# Battery_Detector_v1_0.net
KiCad netlist of a schematic drawn in EAGLE
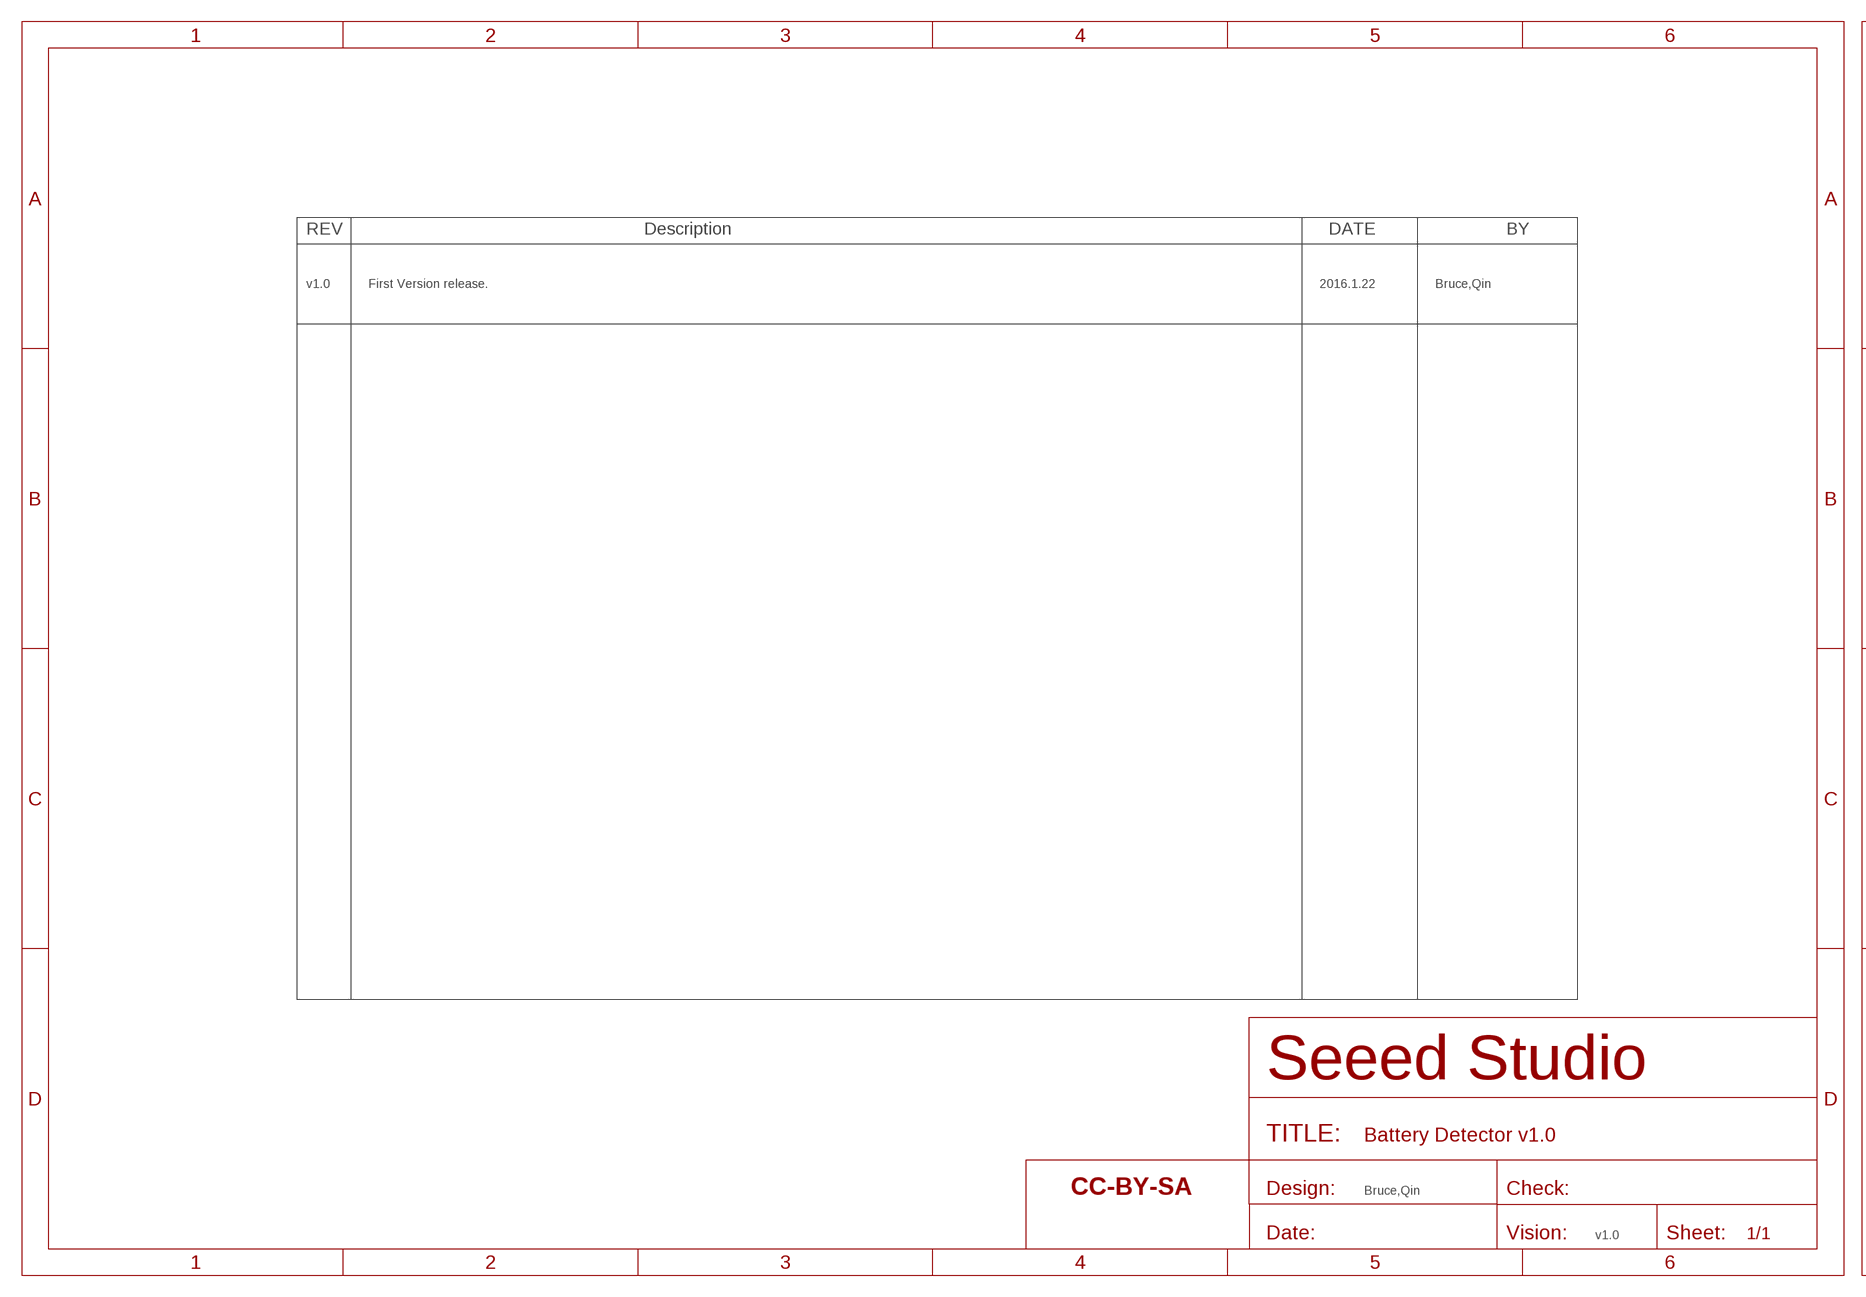
[diagram p0: schematic, sheet 1, part 1 of 2]
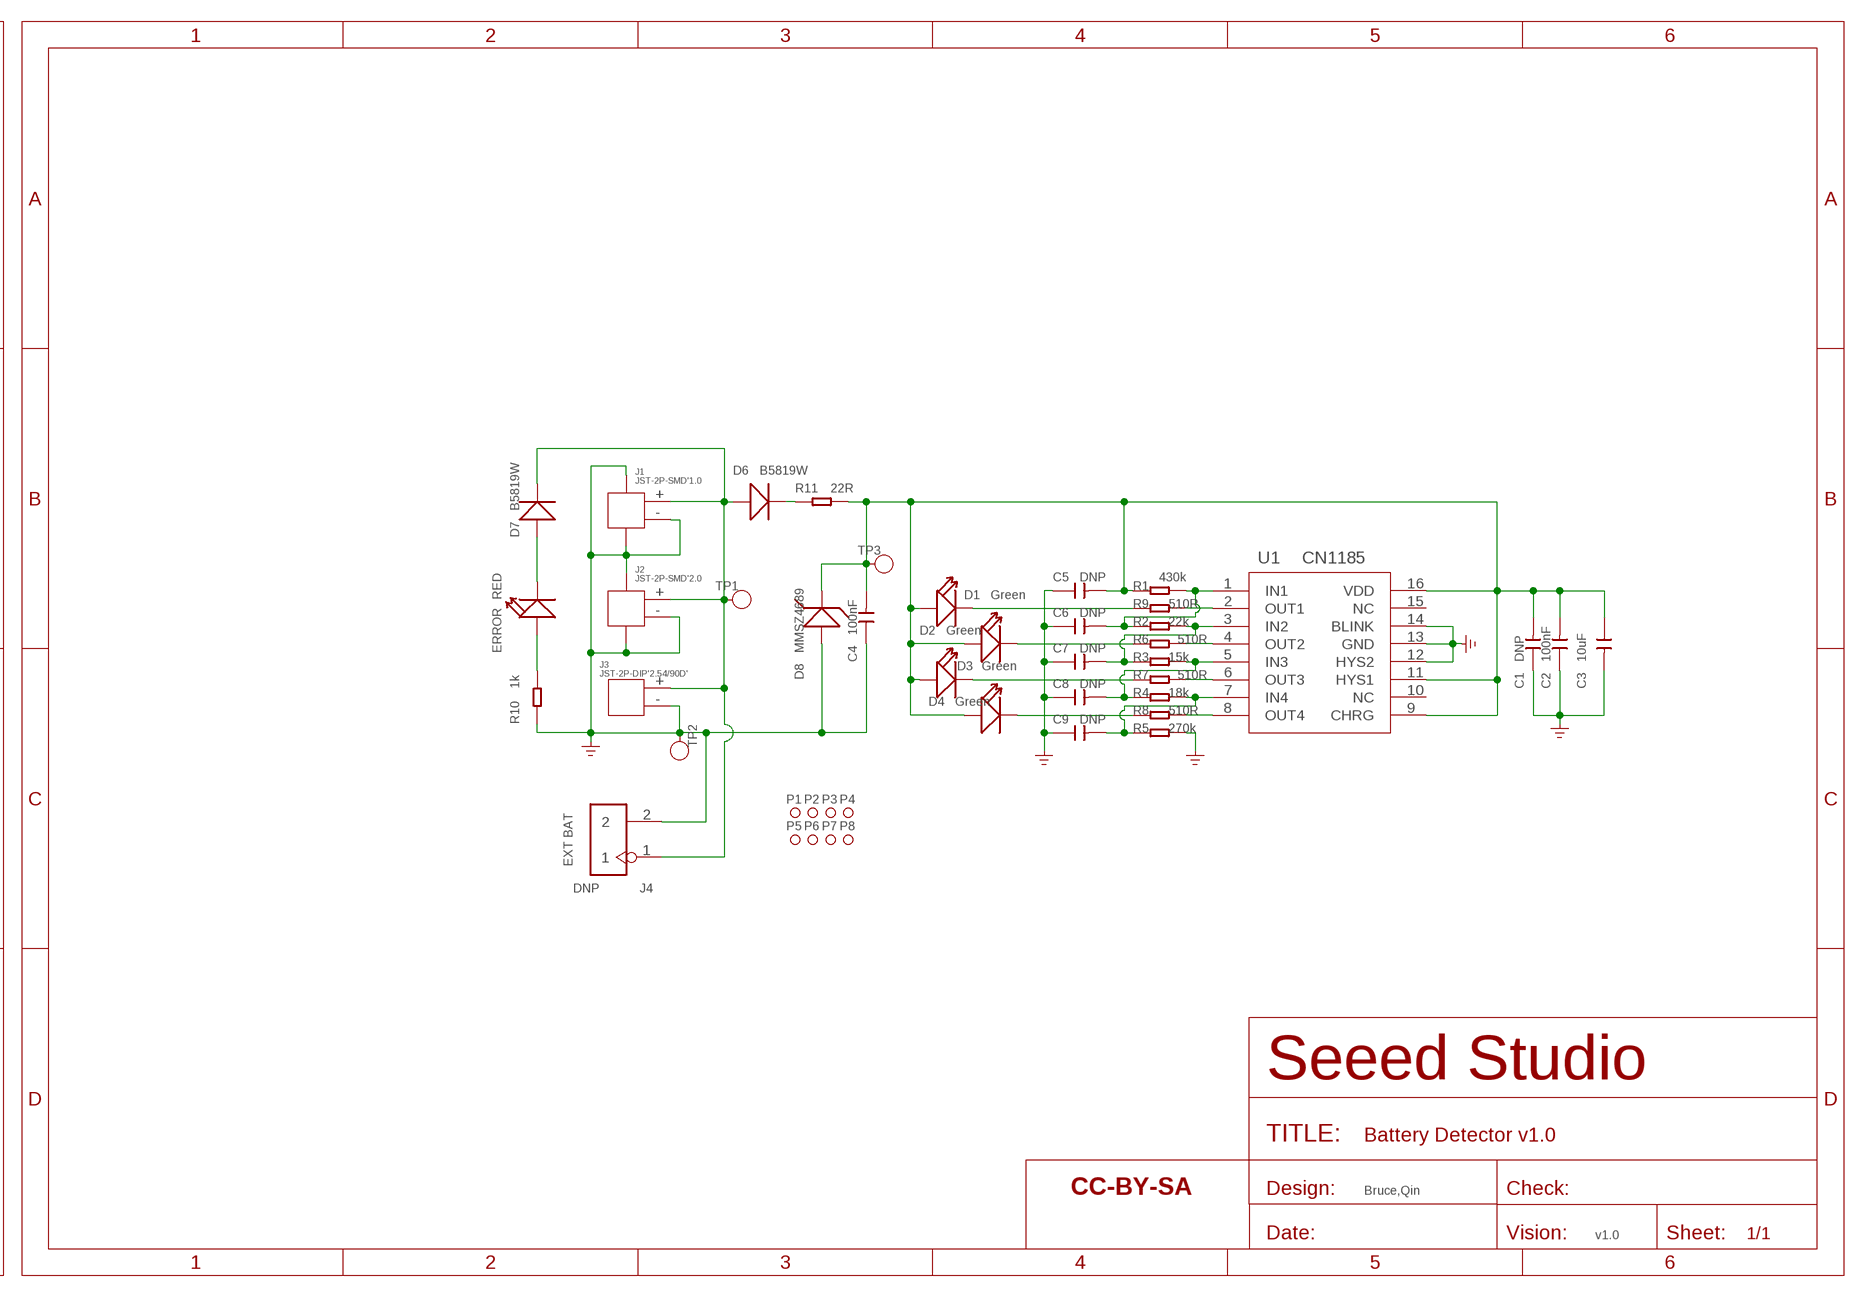
[diagram p1: schematic, sheet 1, part 2 of 2]

(export (version "E")
  (design (tool "Eeschema 10.0.6"))
  (components
    (comp (ref "C1")
      (value "DNP")
      (footprint "eagle-import:C0603")
      (libsource (lib "eagle-import") (part "CAP-0603"))
    )
    (comp (ref "C2")
      (value "100nF")
      (footprint "eagle-import:C0603")
      (libsource (lib "eagle-import") (part "CAP-0603"))
    )
    (comp (ref "C3")
      (value "10uF")
      (footprint "eagle-import:C0805")
      (libsource (lib "eagle-import") (part "CAP-0805"))
    )
    (comp (ref "C4")
      (value "100nF")
      (footprint "eagle-import:C0603")
      (libsource (lib "eagle-import") (part "CAP-0603"))
    )
    (comp (ref "C5")
      (value "DNP")
      (footprint "eagle-import:C0603")
      (libsource (lib "eagle-import") (part "CAP-0603"))
    )
    (comp (ref "C6")
      (value "DNP")
      (footprint "eagle-import:C0603")
      (libsource (lib "eagle-import") (part "CAP-0603"))
    )
    (comp (ref "C7")
      (value "DNP")
      (footprint "eagle-import:C0603")
      (libsource (lib "eagle-import") (part "CAP-0603"))
    )
    (comp (ref "C8")
      (value "DNP")
      (footprint "eagle-import:C0603")
      (libsource (lib "eagle-import") (part "CAP-0603"))
    )
    (comp (ref "C9")
      (value "DNP")
      (footprint "eagle-import:C0603")
      (libsource (lib "eagle-import") (part "CAP-0603"))
    )
    (comp (ref "D1")
      (value "Green")
      (footprint "eagle-import:LED-0603")
      (libsource (lib "eagle-import") (part "LED'0603'"))
    )
    (comp (ref "D2")
      (value "Green")
      (footprint "eagle-import:LED-0603")
      (libsource (lib "eagle-import") (part "LED'0603'"))
    )
    (comp (ref "D3")
      (value "Green")
      (footprint "eagle-import:LED-0603")
      (libsource (lib "eagle-import") (part "LED'0603'"))
    )
    (comp (ref "D4")
      (value "Green")
      (footprint "eagle-import:LED-0603")
      (libsource (lib "eagle-import") (part "LED'0603'"))
    )
    (comp (ref "D6")
      (value "B5819W")
      (footprint "eagle-import:SOD-123")
      (libsource (lib "eagle-import") (part "DIODE'1206'"))
    )
    (comp (ref "D7")
      (value "B5819W")
      (footprint "eagle-import:SOD-123")
      (libsource (lib "eagle-import") (part "DIODE'1206'"))
    )
    (comp (ref "D8")
      (value "MMSZ4689")
      (footprint "eagle-import:SOD-123")
      (libsource (lib "eagle-import") (part "D-ZENER-2P'MMSZ4689-V'"))
    )
    (comp (ref "ERROR")
      (value "RED")
      (footprint "eagle-import:LED-0603")
      (libsource (lib "eagle-import") (part "LED'0603'"))
    )
    (comp (ref "FR1")
      (value "SEEEDSTUDIO-OPEN-SCH-FRAME")
      (footprint "eagle-import:SEEEDSTUDIO-PCB-FRAME")
      (libsource (lib "eagle-import") (part "SEEEDSTUDIO-OPEN-SCH-FRAME"))
    )
    (comp (ref "FR2")
      (value "SEEEDSTUDIO-OPEN-SCH-FRAME")
      (footprint "eagle-import:SEEEDSTUDIO-PCB-FRAME")
      (libsource (lib "eagle-import") (part "SEEEDSTUDIO-OPEN-SCH-FRAME"))
    )
    (comp (ref "J1")
      (value "JST-2P-SMD'1.0")
      (footprint "eagle-import:HW2-SMD-1.0-90D")
      (libsource (lib "eagle-import") (part "JST-2P-SMD'1.0'"))
    )
    (comp (ref "J2")
      (value "JST-2P-SMD'2.0")
      (footprint "eagle-import:HW2-SMD-2.0-90D")
      (libsource (lib "eagle-import") (part "JST-2P-SMD'2.0'"))
    )
    (comp (ref "J3")
      (value "JST-2P-DIP'2.54/90D'")
      (footprint "eagle-import:JST2-2.54-90D")
      (libsource (lib "eagle-import") (part "JST-2P-DIP'2.54/90D'"))
    )
    (comp (ref "J4")
      (value "DNP")
      (footprint "eagle-import:H2-2.54")
      (libsource (lib "eagle-import") (part "HEADER-2P-65/35MIL"))
    )
    (comp (ref "P1")
      (value "MARK-1.0'ANNULAR'")
      (footprint "eagle-import:ROUND-MARK-1.0")
      (fields (field (name "PARTNO") "DNP"))
      (libsource (lib "eagle-import") (part "MARK-1.0'ANNULAR'"))
    )
    (comp (ref "P2")
      (value "MARK-1.0'ANNULAR'")
      (footprint "eagle-import:ROUND-MARK-1.0")
      (fields (field (name "PARTNO") "DNP"))
      (libsource (lib "eagle-import") (part "MARK-1.0'ANNULAR'"))
    )
    (comp (ref "P3")
      (value "MARK-1.0'ANNULAR'")
      (footprint "eagle-import:ROUND-MARK-1.0")
      (fields (field (name "PARTNO") "DNP"))
      (libsource (lib "eagle-import") (part "MARK-1.0'ANNULAR'"))
    )
    (comp (ref "P4")
      (value "MARK-1.0'ANNULAR'")
      (footprint "eagle-import:ROUND-MARK-1.0")
      (fields (field (name "PARTNO") "DNP"))
      (libsource (lib "eagle-import") (part "MARK-1.0'ANNULAR'"))
    )
    (comp (ref "P5")
      (value "MARK-1.0'ANNULAR'")
      (footprint "eagle-import:ROUND-MARK-1.0")
      (fields (field (name "PARTNO") "DNP"))
      (libsource (lib "eagle-import") (part "MARK-1.0'ANNULAR'"))
    )
    (comp (ref "P6")
      (value "MARK-1.0'ANNULAR'")
      (footprint "eagle-import:ROUND-MARK-1.0")
      (fields (field (name "PARTNO") "DNP"))
      (libsource (lib "eagle-import") (part "MARK-1.0'ANNULAR'"))
    )
    (comp (ref "P7")
      (value "MARK-1.0'ANNULAR'")
      (footprint "eagle-import:ROUND-MARK-1.0")
      (fields (field (name "PARTNO") "DNP"))
      (libsource (lib "eagle-import") (part "MARK-1.0'ANNULAR'"))
    )
    (comp (ref "P8")
      (value "MARK-1.0'ANNULAR'")
      (footprint "eagle-import:ROUND-MARK-1.0")
      (fields (field (name "PARTNO") "DNP"))
      (libsource (lib "eagle-import") (part "MARK-1.0'ANNULAR'"))
    )
    (comp (ref "R1")
      (value "430k")
      (footprint "eagle-import:R0603")
      (libsource (lib "eagle-import") (part "RES-0603"))
    )
    (comp (ref "R2")
      (value "22k")
      (footprint "eagle-import:R0603")
      (libsource (lib "eagle-import") (part "RES-0603"))
    )
    (comp (ref "R3")
      (value "15k")
      (footprint "eagle-import:R0603")
      (libsource (lib "eagle-import") (part "RES-0603"))
    )
    (comp (ref "R4")
      (value "18k")
      (footprint "eagle-import:R0603")
      (libsource (lib "eagle-import") (part "RES-0603"))
    )
    (comp (ref "R5")
      (value "270k")
      (footprint "eagle-import:R0603")
      (libsource (lib "eagle-import") (part "RES-0603"))
    )
    (comp (ref "R6")
      (value "510R")
      (footprint "eagle-import:R0603")
      (libsource (lib "eagle-import") (part "RES-0603"))
    )
    (comp (ref "R7")
      (value "510R")
      (footprint "eagle-import:R0603")
      (libsource (lib "eagle-import") (part "RES-0603"))
    )
    (comp (ref "R8")
      (value "510R")
      (footprint "eagle-import:R0603")
      (libsource (lib "eagle-import") (part "RES-0603"))
    )
    (comp (ref "R9")
      (value "510R")
      (footprint "eagle-import:R0603")
      (libsource (lib "eagle-import") (part "RES-0603"))
    )
    (comp (ref "R10")
      (value "1k")
      (footprint "eagle-import:R0603")
      (libsource (lib "eagle-import") (part "RES-0603"))
    )
    (comp (ref "R11")
      (value "22R")
      (footprint "eagle-import:R0805")
      (libsource (lib "eagle-import") (part "RES-0805"))
    )
    (comp (ref "TP1")
      (value "DNP")
      (footprint "eagle-import:TP-D45MIL")
      (libsource (lib "eagle-import") (part "TEST-POINT'4545'"))
    )
    (comp (ref "TP2")
      (value "DNP")
      (footprint "eagle-import:TP-D45MIL")
      (libsource (lib "eagle-import") (part "TEST-POINT'4545'"))
    )
    (comp (ref "TP3")
      (value "DNP")
      (footprint "eagle-import:TP-D45MIL")
      (libsource (lib "eagle-import") (part "TEST-POINT'4545'"))
    )
    (comp (ref "U1")
      (value "CN1185")
      (footprint "eagle-import:TSSOP16-0.65-5X4.4MM")
      (libsource (lib "eagle-import") (part "CN1185"))
    )
  )
  (nets
    (net (code "1") (name "GND_POWER") (class "Default")
      (node (ref "C1") (pin "1") (pinfunction "1_1") (pintype "passive"))
      (node (ref "C2") (pin "1") (pinfunction "1_1") (pintype "passive"))
      (node (ref "C3") (pin "2") (pinfunction "2_2") (pintype "passive"))
      (node (ref "C4") (pin "1") (pinfunction "1_1") (pintype "passive"))
      (node (ref "C5") (pin "1") (pinfunction "1_1") (pintype "passive"))
      (node (ref "C6") (pin "1") (pinfunction "1_1") (pintype "passive"))
      (node (ref "C7") (pin "1") (pinfunction "1_1") (pintype "passive"))
      (node (ref "C8") (pin "1") (pinfunction "1_1") (pintype "passive"))
      (node (ref "C9") (pin "1") (pinfunction "1_1") (pintype "passive"))
      (node (ref "D8") (pin "+") (pinfunction "+_+") (pintype "bidirectional"))
      (node (ref "J1") (pin "-") (pinfunction "2_-") (pintype "bidirectional"))
      (node (ref "J1") (pin "3") (pinfunction "3_3") (pintype "bidirectional"))
      (node (ref "J1") (pin "4") (pinfunction "4_4") (pintype "bidirectional"))
      (node (ref "J2") (pin "-") (pinfunction "2_-") (pintype "bidirectional"))
      (node (ref "J2") (pin "3") (pinfunction "3_3") (pintype "bidirectional"))
      (node (ref "J2") (pin "4") (pinfunction "4_4") (pintype "bidirectional"))
      (node (ref "J3") (pin "-") (pinfunction "P$2_-") (pintype "bidirectional"))
      (node (ref "J4") (pin "2") (pinfunction "2_2") (pintype "bidirectional"))
      (node (ref "R10") (pin "2") (pinfunction "2_2") (pintype "passive"))
      (node (ref "R5") (pin "1") (pinfunction "1_1") (pintype "passive"))
      (node (ref "TP2") (pin "T") (pinfunction "T_T") (pintype "bidirectional"))
      (node (ref "U1") (pin "12") (pinfunction "HYS2_12") (pintype "bidirectional"))
      (node (ref "U1") (pin "13") (pinfunction "GND_13") (pintype "power_in"))
      (node (ref "U1") (pin "14") (pinfunction "BLINK_14") (pintype "bidirectional"))
    )
    (net (code "2") (name "Net-(D1-Pad-)") (class "Default")
      (node (ref "D1") (pin "-") (pinfunction "-_-") (pintype "passive"))
      (node (ref "R9") (pin "2") (pinfunction "2_2") (pintype "passive"))
    )
    (net (code "3") (name "Net-(D2-Pad-)") (class "Default")
      (node (ref "D2") (pin "-") (pinfunction "-_-") (pintype "passive"))
      (node (ref "R6") (pin "2") (pinfunction "2_2") (pintype "passive"))
    )
    (net (code "4") (name "Net-(D3-Pad-)") (class "Default")
      (node (ref "D3") (pin "-") (pinfunction "-_-") (pintype "passive"))
      (node (ref "R7") (pin "2") (pinfunction "2_2") (pintype "passive"))
    )
    (net (code "5") (name "Net-(D4-Pad-)") (class "Default")
      (node (ref "D4") (pin "-") (pinfunction "-_-") (pintype "passive"))
      (node (ref "R8") (pin "2") (pinfunction "2_2") (pintype "passive"))
    )
    (net (code "6") (name "Net-(D6-Pad-)") (class "Default")
      (node (ref "D6") (pin "-") (pinfunction "-_-") (pintype "passive"))
      (node (ref "R11") (pin "2") (pinfunction "2_2") (pintype "passive"))
    )
    (net (code "7") (name "Net-(D7-Pad+)") (class "Default")
      (node (ref "D7") (pin "+") (pinfunction "+_+") (pintype "passive"))
      (node (ref "ERROR") (pin "-") (pinfunction "-_-") (pintype "passive"))
    )
    (net (code "8") (name "Net-(ERROR-Pad+)") (class "Default")
      (node (ref "ERROR") (pin "+") (pinfunction "+_+") (pintype "passive"))
      (node (ref "R10") (pin "1") (pinfunction "1_1") (pintype "passive"))
    )
    (net (code "9") (name "Net-(J1-1)") (class "Default")
      (node (ref "D6") (pin "+") (pinfunction "+_+") (pintype "passive"))
      (node (ref "D7") (pin "-") (pinfunction "-_-") (pintype "passive"))
      (node (ref "J1") (pin "+") (pinfunction "1_+") (pintype "bidirectional"))
      (node (ref "J2") (pin "+") (pinfunction "1_+") (pintype "bidirectional"))
      (node (ref "J3") (pin "+") (pinfunction "P$1_+") (pintype "bidirectional"))
      (node (ref "J4") (pin "1") (pinfunction "1_1") (pintype "bidirectional"))
      (node (ref "TP1") (pin "T") (pinfunction "T_T") (pintype "bidirectional"))
    )
    (net (code "10") (name "Net-(U1-CHRG)") (class "Default")
      (node (ref "C1") (pin "2") (pinfunction "2_2") (pintype "passive"))
      (node (ref "C2") (pin "2") (pinfunction "2_2") (pintype "passive"))
      (node (ref "C3") (pin "1") (pinfunction "1_1") (pintype "passive"))
      (node (ref "C4") (pin "2") (pinfunction "2_2") (pintype "passive"))
      (node (ref "C5") (pin "2") (pinfunction "2_2") (pintype "passive"))
      (node (ref "D1") (pin "+") (pinfunction "+_+") (pintype "passive"))
      (node (ref "D2") (pin "+") (pinfunction "+_+") (pintype "passive"))
      (node (ref "D3") (pin "+") (pinfunction "+_+") (pintype "passive"))
      (node (ref "D4") (pin "+") (pinfunction "+_+") (pintype "passive"))
      (node (ref "D8") (pin "-") (pinfunction "-_-") (pintype "bidirectional"))
      (node (ref "R1") (pin "2") (pinfunction "2_2") (pintype "passive"))
      (node (ref "R11") (pin "1") (pinfunction "1_1") (pintype "passive"))
      (node (ref "TP3") (pin "T") (pinfunction "T_T") (pintype "bidirectional"))
      (node (ref "U1") (pin "11") (pinfunction "HYS1_11") (pintype "bidirectional"))
      (node (ref "U1") (pin "16") (pinfunction "VDD_16") (pintype "power_in"))
      (node (ref "U1") (pin "9") (pinfunction "CHRG_9") (pintype "bidirectional"))
    )
    (net (code "11") (name "Net-(U1-IN1)") (class "Default")
      (node (ref "C6") (pin "2") (pinfunction "2_2") (pintype "passive"))
      (node (ref "R1") (pin "1") (pinfunction "1_1") (pintype "passive"))
      (node (ref "R2") (pin "2") (pinfunction "2_2") (pintype "passive"))
      (node (ref "U1") (pin "1") (pinfunction "IN1_1") (pintype "bidirectional"))
    )
    (net (code "12") (name "Net-(U1-IN2)") (class "Default")
      (node (ref "C7") (pin "2") (pinfunction "2_2") (pintype "passive"))
      (node (ref "R2") (pin "1") (pinfunction "1_1") (pintype "passive"))
      (node (ref "R3") (pin "2") (pinfunction "2_2") (pintype "passive"))
      (node (ref "U1") (pin "3") (pinfunction "IN2_3") (pintype "bidirectional"))
    )
    (net (code "13") (name "Net-(U1-IN3)") (class "Default")
      (node (ref "C8") (pin "2") (pinfunction "2_2") (pintype "passive"))
      (node (ref "R3") (pin "1") (pinfunction "1_1") (pintype "passive"))
      (node (ref "R4") (pin "2") (pinfunction "2_2") (pintype "passive"))
      (node (ref "U1") (pin "5") (pinfunction "IN3_5") (pintype "input"))
    )
    (net (code "14") (name "Net-(U1-IN4)") (class "Default")
      (node (ref "C9") (pin "2") (pinfunction "2_2") (pintype "passive"))
      (node (ref "R4") (pin "1") (pinfunction "1_1") (pintype "passive"))
      (node (ref "R5") (pin "2") (pinfunction "2_2") (pintype "passive"))
      (node (ref "U1") (pin "7") (pinfunction "IN4_7") (pintype "bidirectional"))
    )
    (net (code "15") (name "Net-(U1-OUT1)") (class "Default")
      (node (ref "R9") (pin "1") (pinfunction "1_1") (pintype "passive"))
      (node (ref "U1") (pin "2") (pinfunction "OUT1_2") (pintype "bidirectional"))
    )
    (net (code "16") (name "Net-(U1-OUT2)") (class "Default")
      (node (ref "R6") (pin "1") (pinfunction "1_1") (pintype "passive"))
      (node (ref "U1") (pin "4") (pinfunction "OUT2_4") (pintype "bidirectional"))
    )
    (net (code "17") (name "Net-(U1-OUT3)") (class "Default")
      (node (ref "R7") (pin "1") (pinfunction "1_1") (pintype "passive"))
      (node (ref "U1") (pin "6") (pinfunction "OUT3_6") (pintype "bidirectional"))
    )
    (net (code "18") (name "Net-(U1-OUT4)") (class "Default")
      (node (ref "R8") (pin "1") (pinfunction "1_1") (pintype "passive"))
      (node (ref "U1") (pin "8") (pinfunction "OUT4_8") (pintype "bidirectional"))
    )
    (net (code "19") (name "unconnected-(U1-NC-Pad10)") (class "Default")
      (node (ref "U1") (pin "10") (pinfunction "NC_10") (pintype "no_connect"))
    )
    (net (code "20") (name "unconnected-(U1-NC-Pad15)") (class "Default")
      (node (ref "U1") (pin "15") (pinfunction "NC_15") (pintype "no_connect"))
    )
  )
)
